# SCH_BOTTOM_BOARD.net
KiCad netlist of a schematic drawn in EasyEDA
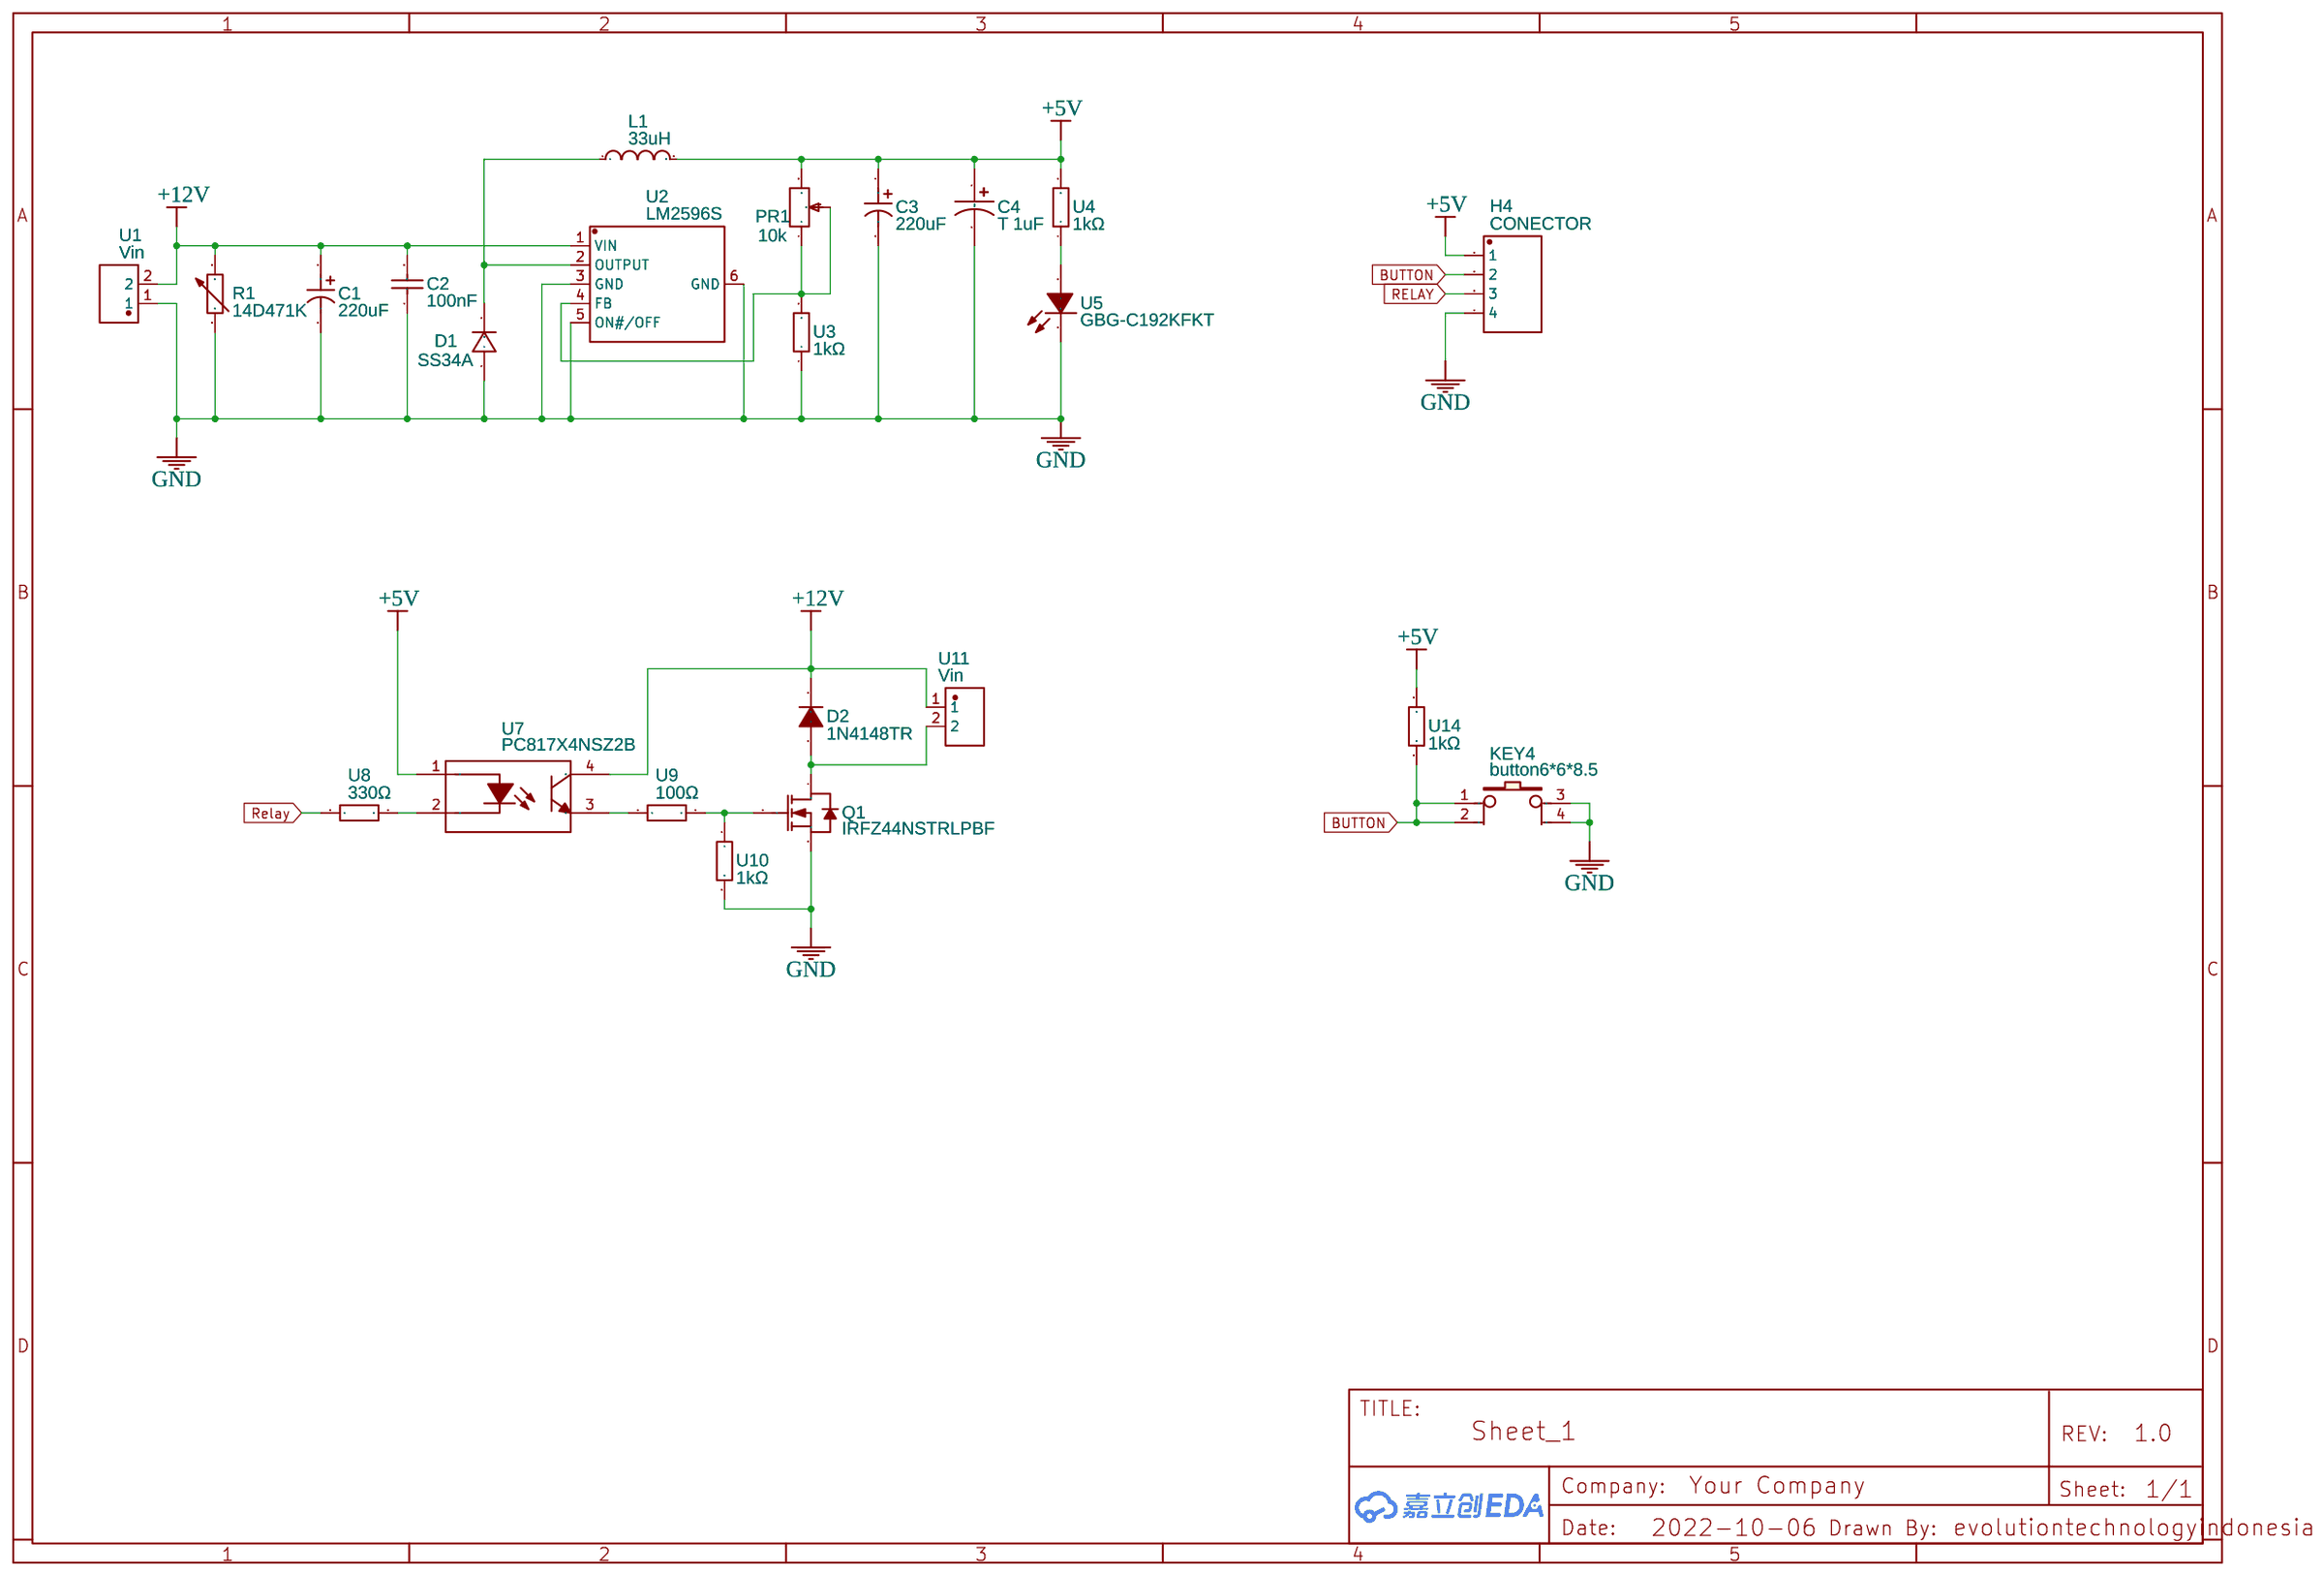
[diagram p0: schematic sheet]

(export (version "E")
  (design (tool "Eeschema 10.0.6"))
  (components
    (comp (ref "C1")
      (value "220uF")
      (fields
        (field (name "BOM_Manufacturer Part") "RVT220UF50V67RV0021")
        (field (name "BOM_Supplier Part") "C2887271")
      )
      (libsource (lib "") (part "RVT220UF50V67RV0021"))
    )
    (comp (ref "C2")
      (value "100nF")
      (fields
        (field (name "BOM_Manufacturer Part") "0805B104J500NT")
        (field (name "BOM_Supplier Part") "C29926")
      )
      (libsource (lib "") (part "0805B104J500NT"))
    )
    (comp (ref "C3")
      (value "220uF")
      (fields
        (field (name "BOM_Manufacturer Part") "RVT220UF50V67RV0021")
        (field (name "BOM_Supplier Part") "C2887271")
      )
      (libsource (lib "") (part "RVT220UF50V67RV0021_1"))
    )
    (comp (ref "C4")
      (value "T 1uF")
      (fields
        (field (name "BOM_Manufacturer Part") "293D156X9016C2TE3")
        (field (name "BOM_Supplier Part") "C506624")
      )
      (libsource (lib "") (part "293D156X9016C2TE3"))
    )
    (comp (ref "D1")
      (value "SS34A")
      (fields (field (name "BOM_Supplier Part") "C211775"))
      (libsource (lib "") (part "SS34A"))
    )
    (comp (ref "D2")
      (value "1N4148TR")
      (fields (field (name "BOM_Supplier Part") "C84410"))
      (libsource (lib "") (part "1N4148TR"))
    )
    (comp (ref "H4")
      (value "CONECTOR")
      (fields
        (field (name "BOM_Manufacturer Part") "B-2100S04P-A110")
        (field (name "BOM_Supplier Part") "C124378")
      )
      (libsource (lib "") (part "Header-Male-2.54_1x4"))
    )
    (comp (ref "KEY4")
      (value "button6*6*8.5")
      (fields (field (name "BOM_Supplier Part") "C59980"))
      (libsource (lib "") (part "button6*6*8.5"))
    )
    (comp (ref "L1")
      (value "33uH")
      (fields
        (field (name "BOM_Manufacturer Part") "SMDRH104R-330MT")
        (field (name "BOM_Supplier Part") "C9936")
      )
      (libsource (lib "") (part "SMDRH104R-330MT"))
    )
    (comp (ref "PR1")
      (value "10k")
      (fields (field (name "BOM_Manufacturer Part") "3296W-1-502") (field (name "BOM_Supplier Part") "C5032"))
      (libsource (lib "") (part "3296W-1-502_C5032"))
    )
    (comp (ref "Q1")
      (value "IRFZ44NSTRLPBF")
      (fields (field (name "BOM_Supplier Part") "C58228"))
      (libsource (lib "") (part "IRFZ44NSTRLPBF"))
    )
    (comp (ref "R1")
      (value "14D471K")
      (fields (field (name "BOM_Supplier Part") "C111189"))
      (libsource (lib "") (part "14D471K"))
    )
    (comp (ref "U1")
      (value "Vin")
      (fields
        (field (name "BOM_Manufacturer Part") "KF129-5.08-2P")
        (field (name "BOM_Supplier Part") "C475092")
      )
      (libsource (lib "") (part "KF129-5.08-2P_1"))
    )
    (comp (ref "U2")
      (value "LM2596S")
      (fields
        (field (name "BOM_Manufacturer Part") "LM2596S-5.0/TR")
        (field (name "BOM_Supplier Part") "C194349")
      )
      (libsource (lib "") (part "LM2596S-5.0/TR"))
    )
    (comp (ref "U3")
      (value "1kΩ")
      (fields
        (field (name "BOM_Manufacturer Part") "HPCR0805F13K0K9")
        (field (name "BOM_Supplier Part") "C365241")
      )
      (libsource (lib "") (part "HPCR0805F13K0K9"))
    )
    (comp (ref "U4")
      (value "1kΩ")
      (fields
        (field (name "BOM_Manufacturer Part") "HPCR0805F13K0K9")
        (field (name "BOM_Supplier Part") "C365241")
      )
      (libsource (lib "") (part "HPCR0805F13K0K9"))
    )
    (comp (ref "U5")
      (value "GBG-C192KFKT")
      (fields (field (name "BOM_Supplier Part") "C2892159"))
      (libsource (lib "") (part "GBG-C192KFKT"))
    )
    (comp (ref "U7")
      (value "PC817X4NSZ2B")
      (fields (field (name "BOM_Supplier Part") "C394683"))
      (libsource (lib "") (part "PC817X4NSZ2B"))
    )
    (comp (ref "U8")
      (value "330Ω")
      (fields
        (field (name "BOM_Manufacturer Part") "HPCR0805F13K0K9")
        (field (name "BOM_Supplier Part") "C365241")
      )
      (libsource (lib "") (part "HPCR0805F13K0K9_1"))
    )
    (comp (ref "U9")
      (value "100Ω")
      (fields
        (field (name "BOM_Manufacturer Part") "HPCR0805F13K0K9")
        (field (name "BOM_Supplier Part") "C365241")
      )
      (libsource (lib "") (part "HPCR0805F13K0K9_1"))
    )
    (comp (ref "U10")
      (value "1kΩ")
      (fields
        (field (name "BOM_Manufacturer Part") "HPCR0805F13K0K9")
        (field (name "BOM_Supplier Part") "C365241")
      )
      (libsource (lib "") (part "HPCR0805F13K0K9_2"))
    )
    (comp (ref "U11")
      (value "Vin")
      (fields
        (field (name "BOM_Manufacturer Part") "KF129-5.08-2P")
        (field (name "BOM_Supplier Part") "C475092")
      )
      (libsource (lib "") (part "KF129-5.08-2P"))
    )
    (comp (ref "U14")
      (value "1kΩ")
      (fields
        (field (name "BOM_Manufacturer Part") "HPCR0805F13K0K9")
        (field (name "BOM_Supplier Part") "C365241")
      )
      (libsource (lib "") (part "HPCR0805F13K0K9_2"))
    )
  )
  (nets
    (net (code "1") (name "+5V") (class "Default")
      (node (ref "C3") (pin "1") (pinfunction "1_1") (pintype "input"))
      (node (ref "C4") (pin "1") (pinfunction "1_1") (pintype "unspecified"))
      (node (ref "H4") (pin "1") (pinfunction "1_1") (pintype "unspecified"))
      (node (ref "L1") (pin "2") (pinfunction "2_2") (pintype "unspecified"))
      (node (ref "PR1") (pin "3") (pinfunction "3_3") (pintype "input"))
      (node (ref "U14") (pin "1") (pinfunction "1_1") (pintype "unspecified"))
      (node (ref "U4") (pin "2") (pinfunction "2_2") (pintype "unspecified"))
      (node (ref "U7") (pin "1") (pinfunction "AN_1") (pintype "unspecified"))
    )
    (net (code "2") (name "+12V") (class "Default")
      (node (ref "C1") (pin "1") (pinfunction "1_1") (pintype "input"))
      (node (ref "C2") (pin "2") (pinfunction "2_2") (pintype "input"))
      (node (ref "D2") (pin "1") (pinfunction "C_1") (pintype "unspecified"))
      (node (ref "R1") (pin "2") (pinfunction "2_2") (pintype "unspecified"))
      (node (ref "U1") (pin "2") (pinfunction "2_2") (pintype "unspecified"))
      (node (ref "U11") (pin "1") (pinfunction "1_1") (pintype "unspecified"))
      (node (ref "U2") (pin "1") (pinfunction "VIN_1") (pintype "unspecified"))
      (node (ref "U7") (pin "4") (pinfunction "COL_4") (pintype "unspecified"))
    )
    (net (code "3") (name "BUTTON") (class "Default")
      (node (ref "H4") (pin "2") (pinfunction "2_2") (pintype "unspecified"))
      (node (ref "KEY4") (pin "1") (pinfunction "1_1") (pintype "input"))
      (node (ref "KEY4") (pin "2") (pinfunction "2_2") (pintype "input"))
      (node (ref "U14") (pin "2") (pinfunction "2_2") (pintype "unspecified"))
    )
    (net (code "4") (name "GND") (class "Default")
      (node (ref "C1") (pin "2") (pinfunction "2_2") (pintype "input"))
      (node (ref "C2") (pin "1") (pinfunction "1_1") (pintype "input"))
      (node (ref "C3") (pin "2") (pinfunction "2_2") (pintype "input"))
      (node (ref "C4") (pin "2") (pinfunction "2_2") (pintype "unspecified"))
      (node (ref "D1") (pin "2") (pinfunction "A_2") (pintype "unspecified"))
      (node (ref "H4") (pin "4") (pinfunction "4_4") (pintype "unspecified"))
      (node (ref "KEY4") (pin "3") (pinfunction "3_3") (pintype "input"))
      (node (ref "KEY4") (pin "4") (pinfunction "4_4") (pintype "input"))
      (node (ref "Q1") (pin "3") (pinfunction "S_3") (pintype "unspecified"))
      (node (ref "R1") (pin "1") (pinfunction "1_1") (pintype "unspecified"))
      (node (ref "U1") (pin "1") (pinfunction "1_1") (pintype "unspecified"))
      (node (ref "U10") (pin "2") (pinfunction "2_2") (pintype "unspecified"))
      (node (ref "U2") (pin "3") (pinfunction "GND_3") (pintype "unspecified"))
      (node (ref "U2") (pin "5") (pinfunction "ON#/OFF_5") (pintype "unspecified"))
      (node (ref "U2") (pin "6") (pinfunction "GND_6") (pintype "unspecified"))
      (node (ref "U3") (pin "1") (pinfunction "1_1") (pintype "unspecified"))
      (node (ref "U5") (pin "1") (pinfunction "C_1") (pintype "unspecified"))
    )
    (net (code "5") (name "Net-(D1-C)") (class "Default")
      (node (ref "D1") (pin "1") (pinfunction "C_1") (pintype "unspecified"))
      (node (ref "L1") (pin "1") (pinfunction "1_1") (pintype "unspecified"))
      (node (ref "U2") (pin "2") (pinfunction "OUTPUT_2") (pintype "unspecified"))
    )
    (net (code "6") (name "Net-(D2-A)") (class "Default")
      (node (ref "D2") (pin "2") (pinfunction "A_2") (pintype "unspecified"))
      (node (ref "Q1") (pin "4") (pinfunction "D_4") (pintype "unspecified"))
      (node (ref "U11") (pin "2") (pinfunction "2_2") (pintype "unspecified"))
    )
    (net (code "7") (name "Net-(Q1-G)") (class "Default")
      (node (ref "Q1") (pin "1") (pinfunction "G_1") (pintype "unspecified"))
      (node (ref "U10") (pin "1") (pinfunction "1_1") (pintype "unspecified"))
      (node (ref "U9") (pin "1") (pinfunction "1_1") (pintype "unspecified"))
    )
    (net (code "8") (name "Net-(U2-FB)") (class "Default")
      (node (ref "PR1") (pin "1") (pinfunction "1_1") (pintype "input"))
      (node (ref "PR1") (pin "2") (pinfunction "2_2") (pintype "input"))
      (node (ref "U2") (pin "4") (pinfunction "FB_4") (pintype "unspecified"))
      (node (ref "U3") (pin "2") (pinfunction "2_2") (pintype "unspecified"))
    )
    (net (code "9") (name "Net-(U5-A)") (class "Default")
      (node (ref "U4") (pin "1") (pinfunction "1_1") (pintype "unspecified"))
      (node (ref "U5") (pin "2") (pinfunction "A_2") (pintype "unspecified"))
    )
    (net (code "10") (name "Net-(U7-CAT)") (class "Default")
      (node (ref "U7") (pin "2") (pinfunction "CAT_2") (pintype "unspecified"))
      (node (ref "U8") (pin "1") (pinfunction "1_1") (pintype "unspecified"))
    )
    (net (code "11") (name "Net-(U7-EM)") (class "Default")
      (node (ref "U7") (pin "3") (pinfunction "EM_3") (pintype "unspecified"))
      (node (ref "U9") (pin "2") (pinfunction "2_2") (pintype "unspecified"))
    )
    (net (code "12") (name "RELAY") (class "Default")
      (node (ref "H4") (pin "3") (pinfunction "3_3") (pintype "unspecified"))
    )
    (net (code "13") (name "Relay") (class "Default")
      (node (ref "U8") (pin "2") (pinfunction "2_2") (pintype "unspecified"))
    )
  )
)
